# PCM2706_CODEC_MAIN.net
KiCad netlist of a schematic drawn in Altium Designer
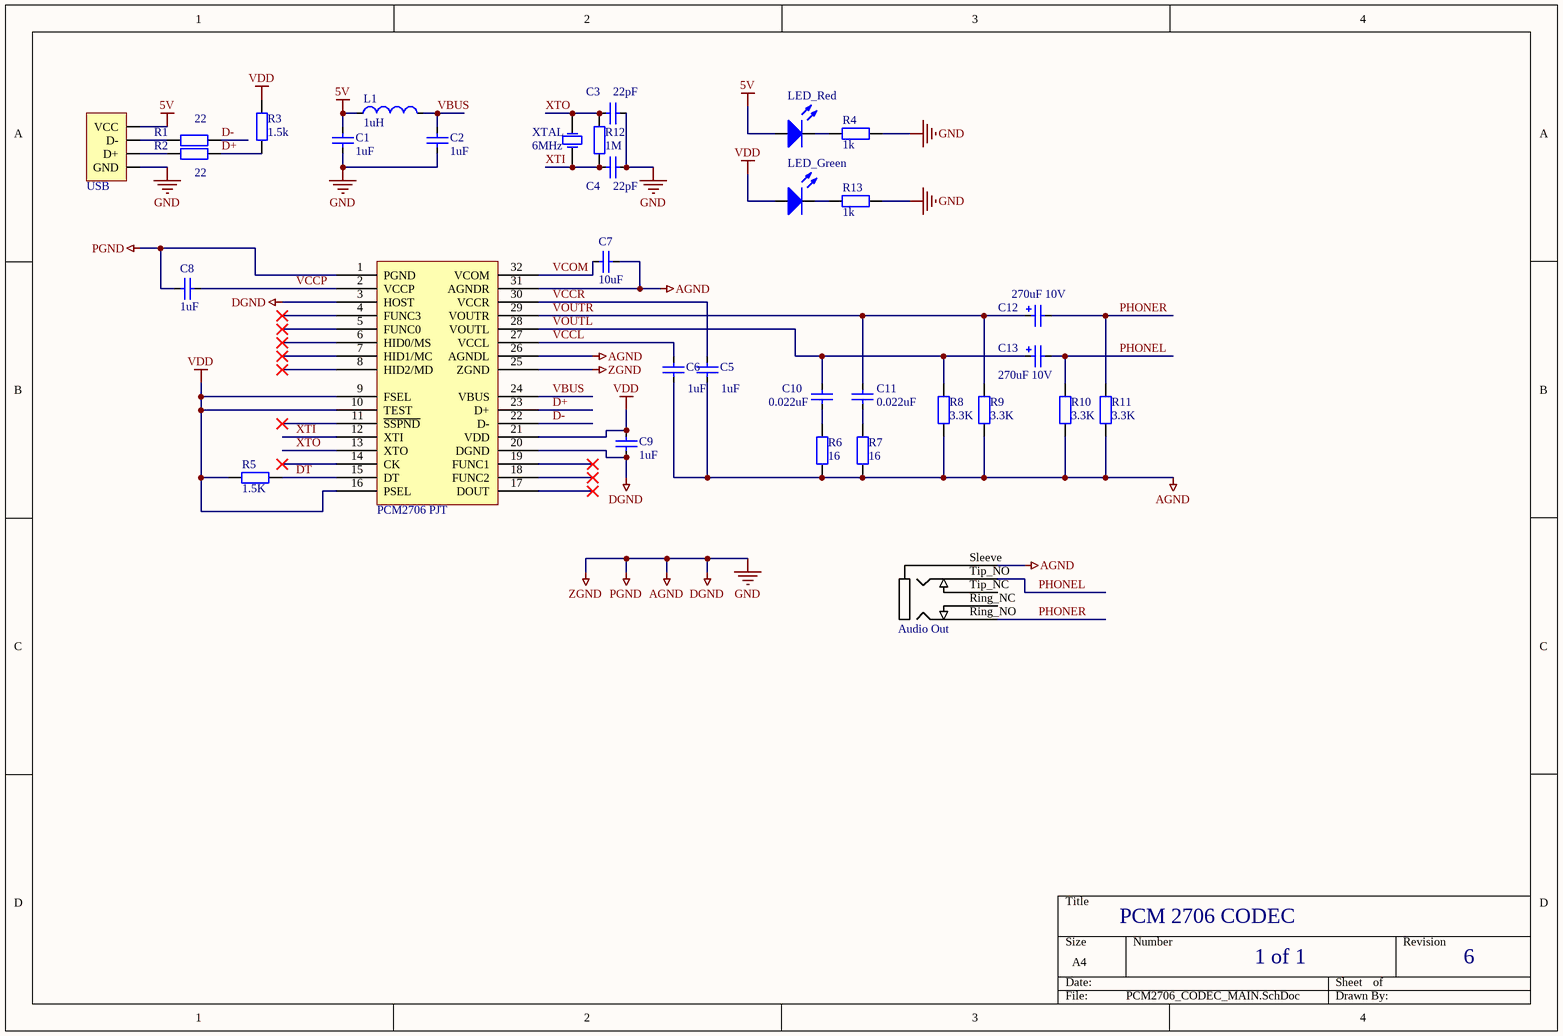
[diagram p0: PCM2706_CODEC_MAIN.SchDoc]

(export (version "E")
  (design (tool "Eeschema 10.0.6"))
  (components
    (comp (ref "Audio Out")
      (value "Generic 3.5 PhoneJack 5 Pin through-hole")
      (footprint "3.5 PhoneJack 5 Pin")
      (libsource (lib "SCH_Connector") (part "Generic 3.5 PhoneJack 5 Pin through-hole"))
    )
    (comp (ref "C1")
      (value "1uF")
      (footprint "PCB_Passive:CAP_0603")
      (description "Capacitor")
      (fields (field (name "Comment") "Cap_0603"))
      (libsource (lib "SCH_Passive") (part "Cap_0603"))
    )
    (comp (ref "C2")
      (value "1uF")
      (footprint "PCB_Passive:CAP_0603")
      (description "Capacitor")
      (fields (field (name "Comment") "Cap_0603"))
      (libsource (lib "SCH_Passive") (part "Cap_0603"))
    )
    (comp (ref "C3")
      (value "22pF")
      (footprint "PCB_Passive:CAP_0603")
      (description "Capacitor")
      (fields (field (name "Comment") "Cap_0603"))
      (libsource (lib "SCH_Passive") (part "Cap_0603"))
    )
    (comp (ref "C4")
      (value "22pF")
      (footprint "PCB_Passive:CAP_0603")
      (description "Capacitor")
      (fields (field (name "Comment") "Cap_0603"))
      (libsource (lib "SCH_Passive") (part "Cap_0603"))
    )
    (comp (ref "C5")
      (value "1uF")
      (footprint "PCB_Passive:CAP_0603")
      (description "Cap_0603")
      (libsource (lib "SCH_Passive") (part "Cap_0603"))
    )
    (comp (ref "C6")
      (value "1uF")
      (footprint "PCB_Passive:CAP_0603")
      (description "Cap_0603")
      (libsource (lib "SCH_Passive") (part "Cap_0603"))
    )
    (comp (ref "C7")
      (value "10uF")
      (footprint "PCB_Passive:CAP_0603")
      (description "Cap_0603")
      (libsource (lib "SCH_Passive") (part "Cap_0603"))
    )
    (comp (ref "C8")
      (value "1uF")
      (footprint "PCB_Passive:CAP_0603")
      (description "Cap_0603")
      (libsource (lib "SCH_Passive") (part "Cap_0603"))
    )
    (comp (ref "C9")
      (value "1uF")
      (footprint "PCB_Passive:CAP_0603")
      (description "Cap_0603")
      (libsource (lib "SCH_Passive") (part "Cap_0603"))
    )
    (comp (ref "C10")
      (value "0.022uF")
      (footprint "PCB_Passive:CAP_0603")
      (description "Cap_0603")
      (libsource (lib "SCH_Passive") (part "Cap_0603"))
    )
    (comp (ref "C11")
      (value "0.022uF")
      (footprint "PCB_Passive:CAP_0603")
      (description "Cap_0603")
      (libsource (lib "SCH_Passive") (part "Cap_0603"))
    )
    (comp (ref "C12")
      (value "270uF 10V")
      (footprint "PCB_Passive:CAP_ELEC_F3.5_D8_H11.5")
      (description "Cap_ELEC_8*11.5*3.5")
      (fields (field (name "Comment") "270uF"))
      (libsource (lib "SCH_Passive") (part "Cap_ELEC_8*11.5*3.5"))
    )
    (comp (ref "C13")
      (value "270uF 10V")
      (footprint "PCB_Passive:CAP_ELEC_F3.5_D8_H11.5")
      (description "Cap_ELEC_8*11.5*3.5")
      (fields (field (name "Comment") "270uF"))
      (libsource (lib "SCH_Passive") (part "Cap_ELEC_8*11.5*3.5"))
    )
    (comp (ref "L1")
      (value "1uH")
      (footprint "PCB_Passive:IND_0603")
      (description "Inductor")
      (fields (field (name "Comment") "Ind_0603"))
      (libsource (lib "SCH_Passive") (part "Ind_0603"))
    )
    (comp (ref "LED_Green")
      (value "LED_0603_RED")
      (footprint "PCB_Active:LED_0603_RED")
      (description "LED")
      (libsource (lib "SCH_Active") (part "LED_0603_RED"))
    )
    (comp (ref "LED_Red")
      (value "LED_0603_RED")
      (footprint "PCB_Active:LED_0603_RED")
      (description "LED")
      (libsource (lib "SCH_Active") (part "LED_0603_RED"))
    )
    (comp (ref "PCM2706 PJT")
      (value "PCM2706 PJT")
      (footprint "TI-S-PQFP-N32")
      (description "PCM2706 USB CODEC")
      (libsource (lib "SCH_IC") (part "PCM2706 PJT"))
    )
    (comp (ref "R1")
      (value "22")
      (footprint "PCB_Passive:RES_0603")
      (description "Resistor")
      (fields (field (name "Comment") "Res_0603"))
      (libsource (lib "SCH_Passive") (part "Res_0603"))
    )
    (comp (ref "R2")
      (value "22")
      (footprint "PCB_Passive:RES_0603")
      (description "Resistor")
      (fields (field (name "Comment") "Res_0603"))
      (libsource (lib "SCH_Passive") (part "Res_0603"))
    )
    (comp (ref "R3")
      (value "1.5k")
      (footprint "PCB_Passive:RES_0603")
      (description "Resistor")
      (fields (field (name "Comment") "Res_0603"))
      (libsource (lib "") (part "Res_0603_1"))
    )
    (comp (ref "R4")
      (value "1k")
      (footprint "PCB_Passive:RES_0603")
      (description "Res_0603")
      (libsource (lib "SCH_Passive") (part "Res_0603"))
    )
    (comp (ref "R5")
      (value "1.5K")
      (footprint "PCB_Passive:RES_0603")
      (description "Resistor")
      (libsource (lib "SCH_Passive") (part "Res_0603"))
    )
    (comp (ref "R6")
      (value "16")
      (footprint "PCB_Passive:RES_0603")
      (description "Res_0603")
      (libsource (lib "") (part "Res_0603_1"))
    )
    (comp (ref "R7")
      (value "16")
      (footprint "PCB_Passive:RES_0603")
      (description "Res_0603")
      (libsource (lib "") (part "Res_0603_1"))
    )
    (comp (ref "R8")
      (value "3.3K")
      (footprint "PCB_Passive:RES_0603")
      (description "Res_0603")
      (libsource (lib "") (part "Res_0603_1"))
    )
    (comp (ref "R9")
      (value "3.3K")
      (footprint "PCB_Passive:RES_0603")
      (description "Res_0603")
      (libsource (lib "") (part "Res_0603_1"))
    )
    (comp (ref "R10")
      (value "3.3K")
      (footprint "PCB_Passive:RES_0603")
      (description "Res_0603")
      (libsource (lib "") (part "Res_0603_1"))
    )
    (comp (ref "R11")
      (value "3.3K")
      (footprint "PCB_Passive:RES_0603")
      (description "Res_0603")
      (libsource (lib "") (part "Res_0603_1"))
    )
    (comp (ref "R12")
      (value "1M")
      (footprint "PCB_Passive:RES_0603")
      (description "Resistor")
      (fields (field (name "Comment") "Res_0603"))
      (libsource (lib "") (part "Res_0603_1"))
    )
    (comp (ref "R13")
      (value "1k")
      (footprint "PCB_Passive:RES_0603")
      (description "Res_0603")
      (libsource (lib "SCH_Passive") (part "Res_0603"))
    )
    (comp (ref "USB") (value "USB") (footprint "PCB_USB:USB") (libsource (lib "SCH_USB") (part "USB")))
    (comp (ref "XTAL")
      (value "6MHz")
      (footprint "PCB_Oscillator:XTAL_5032")
      (description "Crystal Oscillator")
      (fields (field (name "Comment") "XTAL_5032") (field (name "PUBLISHER") "Altium Limited"))
      (libsource (lib "SCH_Oscillator") (part "XTAL_5032"))
    )
  )
  (nets
    (net (code "1") (name "/D+") (class "Default")
      (node (ref "PCM2706 PJT") (pin "23") (pinfunction "D+_23") (pintype "passive"))
      (node (ref "R2") (pin "2") (pinfunction "2_2") (pintype "passive"))
      (node (ref "R3") (pin "2") (pinfunction "2_2") (pintype "passive"))
    )
    (net (code "2") (name "/D-") (class "Default")
      (node (ref "PCM2706 PJT") (pin "22") (pinfunction "D-_22") (pintype "passive"))
      (node (ref "R1") (pin "2") (pinfunction "2_2") (pintype "passive"))
    )
    (net (code "3") (name "/DT") (class "Default")
      (node (ref "PCM2706 PJT") (pin "15") (pinfunction "DT_15") (pintype "passive"))
      (node (ref "R5") (pin "2") (pinfunction "2_2") (pintype "passive"))
    )
    (net (code "4") (name "/PHONEL") (class "Default")
      (node (ref "Audio Out") (pin "Tip_NO") (pinfunction "Tip_NO_Tip_NO") (pintype "passive"))
      (node (ref "C13") (pin "2") (pinfunction "2_2") (pintype "passive"))
      (node (ref "R10") (pin "1") (pinfunction "1_1") (pintype "passive"))
    )
    (net (code "5") (name "/PHONER") (class "Default")
      (node (ref "Audio Out") (pin "Ring_NO") (pinfunction "Ring_NO_Ring_NO") (pintype "passive"))
      (node (ref "C12") (pin "2") (pinfunction "2_2") (pintype "passive"))
      (node (ref "R11") (pin "1") (pinfunction "1_1") (pintype "passive"))
    )
    (net (code "6") (name "/VBUS") (class "Default")
      (node (ref "C2") (pin "2") (pinfunction "2_2") (pintype "passive"))
      (node (ref "L1") (pin "2") (pinfunction "2_2") (pintype "passive"))
      (node (ref "PCM2706 PJT") (pin "24") (pinfunction "VBUS_24") (pintype "passive"))
    )
    (net (code "7") (name "/VCCL") (class "Default")
      (node (ref "C6") (pin "2") (pinfunction "2_2") (pintype "passive"))
      (node (ref "PCM2706 PJT") (pin "27") (pinfunction "VCCL_27") (pintype "passive"))
    )
    (net (code "8") (name "/VCCP") (class "Default")
      (node (ref "C8") (pin "1") (pinfunction "1_1") (pintype "passive"))
      (node (ref "PCM2706 PJT") (pin "2") (pinfunction "VCCP_2") (pintype "passive"))
    )
    (net (code "9") (name "/VCCR") (class "Default")
      (node (ref "C5") (pin "2") (pinfunction "2_2") (pintype "passive"))
      (node (ref "PCM2706 PJT") (pin "30") (pinfunction "VCCR_30") (pintype "passive"))
    )
    (net (code "10") (name "/VCOM") (class "Default")
      (node (ref "C7") (pin "2") (pinfunction "2_2") (pintype "passive"))
      (node (ref "PCM2706 PJT") (pin "32") (pinfunction "VCOM_32") (pintype "passive"))
    )
    (net (code "11") (name "/VOUTL") (class "Default")
      (node (ref "C10") (pin "2") (pinfunction "2_2") (pintype "passive"))
      (node (ref "C13") (pin "1") (pinfunction "1_1") (pintype "passive"))
      (node (ref "PCM2706 PJT") (pin "28") (pinfunction "VOUTL_28") (pintype "passive"))
      (node (ref "R8") (pin "1") (pinfunction "1_1") (pintype "passive"))
    )
    (net (code "12") (name "/VOUTR") (class "Default")
      (node (ref "C11") (pin "2") (pinfunction "2_2") (pintype "passive"))
      (node (ref "C12") (pin "1") (pinfunction "1_1") (pintype "passive"))
      (node (ref "PCM2706 PJT") (pin "29") (pinfunction "VOUTR_29") (pintype "passive"))
      (node (ref "R9") (pin "1") (pinfunction "1_1") (pintype "passive"))
    )
    (net (code "13") (name "/XTI") (class "Default")
      (node (ref "C4") (pin "2") (pinfunction "2_2") (pintype "passive"))
      (node (ref "PCM2706 PJT") (pin "12") (pinfunction "XTI_12") (pintype "passive"))
      (node (ref "R12") (pin "2") (pinfunction "2_2") (pintype "passive"))
      (node (ref "XTAL") (pin "1") (pinfunction "OSC1_1") (pintype "passive"))
    )
    (net (code "14") (name "/XTO") (class "Default")
      (node (ref "C3") (pin "2") (pinfunction "2_2") (pintype "passive"))
      (node (ref "PCM2706 PJT") (pin "13") (pinfunction "XTO_13") (pintype "passive"))
      (node (ref "R12") (pin "1") (pinfunction "1_1") (pintype "passive"))
      (node (ref "XTAL") (pin "2") (pinfunction "OSC2_2") (pintype "passive"))
    )
    (net (code "15") (name "5V") (class "Default")
      (node (ref "C1") (pin "2") (pinfunction "2_2") (pintype "passive"))
      (node (ref "L1") (pin "1") (pinfunction "1_1") (pintype "passive"))
      (node (ref "LED_Red") (pin "1") (pinfunction "A_1") (pintype "passive"))
      (node (ref "USB") (pin "1") (pinfunction "VCC_1") (pintype "passive"))
    )
    (net (code "16") (name "AGND") (class "Default")
      (node (ref "Audio Out") (pin "Sleeve") (pinfunction "Sleeve_Sleeve") (pintype "passive"))
      (node (ref "C1") (pin "1") (pinfunction "1_1") (pintype "passive"))
      (node (ref "C2") (pin "1") (pinfunction "1_1") (pintype "passive"))
      (node (ref "C3") (pin "1") (pinfunction "1_1") (pintype "passive"))
      (node (ref "C4") (pin "1") (pinfunction "1_1") (pintype "passive"))
      (node (ref "C5") (pin "1") (pinfunction "1_1") (pintype "passive"))
      (node (ref "C6") (pin "1") (pinfunction "1_1") (pintype "passive"))
      (node (ref "C7") (pin "1") (pinfunction "1_1") (pintype "passive"))
      (node (ref "C8") (pin "2") (pinfunction "2_2") (pintype "passive"))
      (node (ref "C9") (pin "1") (pinfunction "1_1") (pintype "passive"))
      (node (ref "PCM2706 PJT") (pin "1") (pinfunction "PGND_1") (pintype "passive"))
      (node (ref "PCM2706 PJT") (pin "20") (pinfunction "DGND_20") (pintype "passive"))
      (node (ref "PCM2706 PJT") (pin "25") (pinfunction "ZGND_25") (pintype "passive"))
      (node (ref "PCM2706 PJT") (pin "26") (pinfunction "AGNDL_26") (pintype "passive"))
      (node (ref "PCM2706 PJT") (pin "3") (pinfunction "HOST_3") (pintype "passive"))
      (node (ref "PCM2706 PJT") (pin "31") (pinfunction "AGNDR_31") (pintype "passive"))
      (node (ref "R10") (pin "2") (pinfunction "2_2") (pintype "passive"))
      (node (ref "R11") (pin "2") (pinfunction "2_2") (pintype "passive"))
      (node (ref "R13") (pin "2") (pinfunction "2_2") (pintype "passive"))
      (node (ref "R4") (pin "2") (pinfunction "2_2") (pintype "passive"))
      (node (ref "R6") (pin "2") (pinfunction "2_2") (pintype "passive"))
      (node (ref "R7") (pin "2") (pinfunction "2_2") (pintype "passive"))
      (node (ref "R8") (pin "2") (pinfunction "2_2") (pintype "passive"))
      (node (ref "R9") (pin "2") (pinfunction "2_2") (pintype "passive"))
      (node (ref "USB") (pin "4") (pinfunction "GND_4") (pintype "passive"))
    )
    (net (code "17") (name "Net-(C10-Pad1)") (class "Default")
      (node (ref "C10") (pin "1") (pinfunction "1_1") (pintype "passive"))
      (node (ref "R6") (pin "1") (pinfunction "1_1") (pintype "passive"))
    )
    (net (code "18") (name "Net-(C11-Pad1)") (class "Default")
      (node (ref "C11") (pin "1") (pinfunction "1_1") (pintype "passive"))
      (node (ref "R7") (pin "1") (pinfunction "1_1") (pintype "passive"))
    )
    (net (code "19") (name "Net-(LED_Green-K)") (class "Default")
      (node (ref "LED_Green") (pin "2") (pinfunction "K_2") (pintype "passive"))
      (node (ref "R13") (pin "1") (pinfunction "1_1") (pintype "passive"))
    )
    (net (code "20") (name "Net-(LED_Red-K)") (class "Default")
      (node (ref "LED_Red") (pin "2") (pinfunction "K_2") (pintype "passive"))
      (node (ref "R4") (pin "1") (pinfunction "1_1") (pintype "passive"))
    )
    (net (code "21") (name "Net-(USB-D+)") (class "Default")
      (node (ref "R2") (pin "1") (pinfunction "1_1") (pintype "passive"))
      (node (ref "USB") (pin "3") (pinfunction "D+_3") (pintype "passive"))
    )
    (net (code "22") (name "Net-(USB-D-)") (class "Default")
      (node (ref "R1") (pin "1") (pinfunction "1_1") (pintype "passive"))
      (node (ref "USB") (pin "2") (pinfunction "D-_2") (pintype "passive"))
    )
    (net (code "23") (name "VDD") (class "Default")
      (node (ref "C9") (pin "2") (pinfunction "2_2") (pintype "passive"))
      (node (ref "LED_Green") (pin "1") (pinfunction "A_1") (pintype "passive"))
      (node (ref "PCM2706 PJT") (pin "10") (pinfunction "TEST_10") (pintype "passive"))
      (node (ref "PCM2706 PJT") (pin "16") (pinfunction "PSEL_16") (pintype "passive"))
      (node (ref "PCM2706 PJT") (pin "21") (pinfunction "VDD_21") (pintype "passive"))
      (node (ref "PCM2706 PJT") (pin "9") (pinfunction "FSEL_9") (pintype "passive"))
      (node (ref "R3") (pin "1") (pinfunction "1_1") (pintype "passive"))
      (node (ref "R5") (pin "1") (pinfunction "1_1") (pintype "passive"))
    )
    (net (code "24") (name "unconnected-(Audio Out-PadRing_NC)") (class "Default")
      (node (ref "Audio Out") (pin "Ring_NC") (pinfunction "Ring_NC_Ring_NC") (pintype "passive"))
    )
    (net (code "25") (name "unconnected-(Audio Out-PadTip_NC)") (class "Default")
      (node (ref "Audio Out") (pin "Tip_NC") (pinfunction "Tip_NC_Tip_NC") (pintype "passive"))
    )
    (net (code "26") (name "unconnected-(PCM2706 PJT-CK-Pad14)") (class "Default")
      (node (ref "PCM2706 PJT") (pin "14") (pinfunction "CK_14") (pintype "passive+no_connect"))
    )
    (net (code "27") (name "unconnected-(PCM2706 PJT-DOUT-Pad17)") (class "Default")
      (node (ref "PCM2706 PJT") (pin "17") (pinfunction "DOUT_17") (pintype "passive+no_connect"))
    )
    (net (code "28") (name "unconnected-(PCM2706 PJT-FUNC0-Pad5)") (class "Default")
      (node (ref "PCM2706 PJT") (pin "5") (pinfunction "FUNC0_5") (pintype "passive+no_connect"))
    )
    (net (code "29") (name "unconnected-(PCM2706 PJT-FUNC1-Pad19)") (class "Default")
      (node (ref "PCM2706 PJT") (pin "19") (pinfunction "FUNC1_19") (pintype "passive+no_connect"))
    )
    (net (code "30") (name "unconnected-(PCM2706 PJT-FUNC2-Pad18)") (class "Default")
      (node (ref "PCM2706 PJT") (pin "18") (pinfunction "FUNC2_18") (pintype "passive+no_connect"))
    )
    (net (code "31") (name "unconnected-(PCM2706 PJT-FUNC3-Pad4)") (class "Default")
      (node (ref "PCM2706 PJT") (pin "4") (pinfunction "FUNC3_4") (pintype "passive+no_connect"))
    )
    (net (code "32") (name "unconnected-(PCM2706 PJT-HID0{slash}MS-Pad6)") (class "Default")
      (node (ref "PCM2706 PJT") (pin "6") (pinfunction "HID0/MS_6") (pintype "passive+no_connect"))
    )
    (net (code "33") (name "unconnected-(PCM2706 PJT-HID1{slash}MC-Pad7)") (class "Default")
      (node (ref "PCM2706 PJT") (pin "7") (pinfunction "HID1/MC_7") (pintype "passive+no_connect"))
    )
    (net (code "34") (name "unconnected-(PCM2706 PJT-HID2{slash}MD-Pad8)") (class "Default")
      (node (ref "PCM2706 PJT") (pin "8") (pinfunction "HID2/MD_8") (pintype "passive+no_connect"))
    )
    (net (code "35") (name "unconnected-(PCM2706 PJT-~{SSPND}-Pad11)") (class "Default")
      (node (ref "PCM2706 PJT") (pin "11") (pinfunction "~{SSPND}_11") (pintype "passive+no_connect"))
    )
  )
)
